# VibrationMotor.net
KiCad netlist of a schematic drawn in Altium Designer
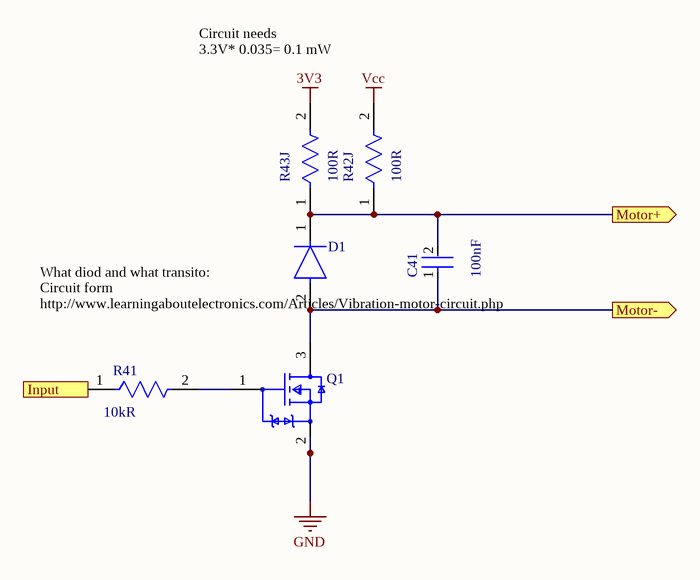
[diagram p0: VibrationMotor.SchDoc]

(export (version "E")
  (design (tool "Eeschema 10.0.6"))
  (components
    (comp (ref "C41")
      (value "EMK107B7104KAHT")
      (footprint "FP-0603-L_1_6_0_1-W_0_8_0-IPC_B")
      (description "None")
      (fields (field (name "CAPACITANCE") "100nF") (field (name "TOLERANCE") "10%"))
      (libsource (lib "Altium Content Vault") (part "02cd4be3c70576c341d710602a673aa"))
    )
    (comp (ref "D1")
      (value "LS4448GS08")
      (footprint "FP-6_560-5006_01-4-MFG")
      (description "DIODE GEN PURP 100V 300MA SOD80")
      (fields
        (field (name "MANUFACTURER") "Vishay")
        (field (name "OCTOPART") "https://octopart.com/ls4448gs08-vishay-55433966")
      )
      (libsource (lib "Altium Content Vault") (part "d7152d700b627762746794eb795d46e"))
    )
    (comp (ref "Q1")
      (value "DMG2302UK-7")
      (footprint "FP-SOT23-MFG")
      (description "MOSFET N-CH 20V 2.8A SOT23")
      (fields
        (field (name "OCTOPART") "https://octopart.com/dmg2302uk-7-diodes+inc.-73850182")
        (field (name "MANUFACTURER") "Diodes Inc.")
      )
      (libsource (lib "Altium Content Vault") (part "87c0c04a04979492222792dd46c39c9"))
    )
    (comp (ref "R41")
      (value "RNCP0603FTD10K0")
      (footprint "FP-RNCP0603-IPC_A")
      (description "10kΩ ±1% 0.125W 0603 High Power Anti-Sulfur Thin Film Chip Resistor")
      (fields (field (name "RESISTANCE") "10kR") (field (name "TOLERANCE") "1%"))
      (libsource (lib "Altium Content Vault") (part "1029c3af85768c4190bb7ad29bc67b5"))
    )
    (comp (ref "R42J")
      (value "ESR03EZPJ101")
      (footprint "FP-ESR03-MFG")
      (description "100Ω ±5% 0.25W 0603 Anti-Surge Chip Resistor AEC-Q200")
      (fields (field (name "TOLERANCE") "5%") (field (name "RESISTANCE") "100R"))
      (libsource (lib "Altium Content Vault") (part "1029c3af85768c4190bb7ad29bc67b5"))
    )
    (comp (ref "R43J")
      (value "ESR03EZPJ101")
      (footprint "FP-ESR03-MFG")
      (description "100Ω ±5% 0.25W 0603 Anti-Surge Chip Resistor AEC-Q200")
      (fields (field (name "TOLERANCE") "5%") (field (name "RESISTANCE") "100R"))
      (libsource (lib "Altium Content Vault") (part "1029c3af85768c4190bb7ad29bc67b5"))
    )
  )
  (nets
    (net (code "1") (name "/Input") (class "Default")
      (node (ref "R41") (pin "1") (pinfunction "1_1") (pintype "passive"))
    )
    (net (code "2") (name "/Motor+") (class "Default")
      (node (ref "C41") (pin "2") (pinfunction "2_2") (pintype "passive"))
      (node (ref "D1") (pin "1") (pinfunction "C_1") (pintype "passive"))
      (node (ref "R42J") (pin "1") (pinfunction "1_1") (pintype "passive"))
      (node (ref "R43J") (pin "1") (pinfunction "1_1") (pintype "passive"))
    )
    (net (code "3") (name "/Motor-") (class "Default")
      (node (ref "C41") (pin "1") (pinfunction "1_1") (pintype "passive"))
      (node (ref "D1") (pin "2") (pinfunction "A_2") (pintype "passive"))
      (node (ref "Q1") (pin "3") (pinfunction "D_3") (pintype "passive"))
    )
    (net (code "4") (name "3V3") (class "Default")
      (node (ref "R43J") (pin "2") (pinfunction "2_2") (pintype "passive"))
    )
    (net (code "5") (name "GND") (class "Default")
      (node (ref "Q1") (pin "2") (pinfunction "S_2") (pintype "passive"))
    )
    (net (code "6") (name "Net-(Q1-G)") (class "Default")
      (node (ref "Q1") (pin "1") (pinfunction "G_1") (pintype "passive"))
      (node (ref "R41") (pin "2") (pinfunction "2_2") (pintype "passive"))
    )
    (net (code "7") (name "Vcc") (class "Default")
      (node (ref "R42J") (pin "2") (pinfunction "2_2") (pintype "passive"))
    )
  )
)
